# Aquarium_Nano.net
KiCad netlist of a schematic drawn in EAGLE
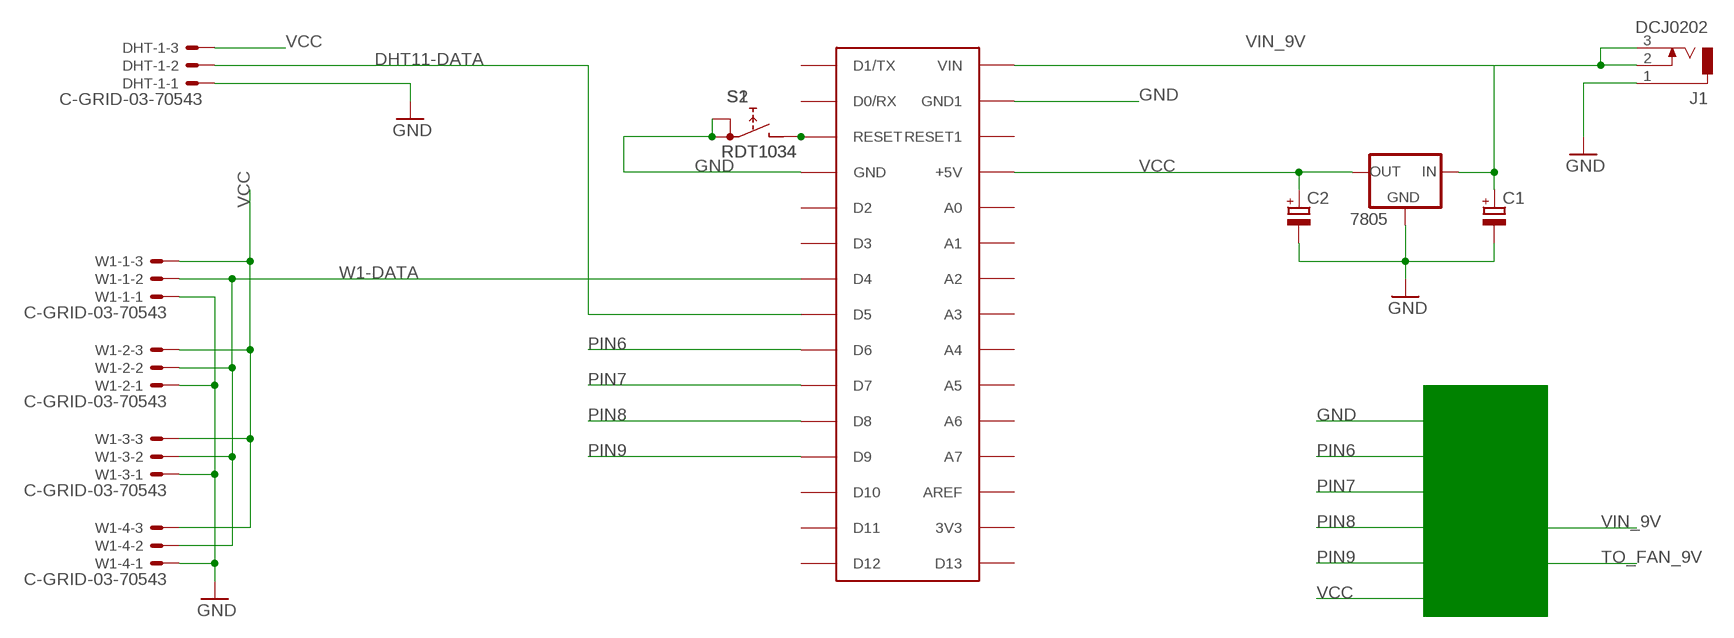
[diagram p0: schematic, sheet 1]

(export (version "E")
  (design (tool "Eeschema 10.0.6"))
  (components
    (comp (ref "7805")
      (value "V_REG_78XX-TO-220")
      (footprint "eagle-import:TO-220-ALT")
      (libsource (lib "eagle-import") (part "V_REG_78XX-TO-220"))
    )
    (comp (ref "C1")
      (value "CPOL-EUE2.5-6")
      (footprint "eagle-import:E2,5-6")
      (libsource (lib "eagle-import") (part "CPOL-EUE2.5-6"))
    )
    (comp (ref "C2")
      (value "CPOL-EUE2.5-6")
      (footprint "eagle-import:E2,5-6")
      (libsource (lib "eagle-import") (part "CPOL-EUE2.5-6"))
    )
    (comp (ref "DHT-1")
      (value "C-GRID-03-70543")
      (footprint "eagle-import:70543-03")
      (libsource (lib "eagle-import") (part "C-GRID-03-70543"))
    )
    (comp (ref "J1")
      (value "DCJ0202")
      (footprint "eagle-import:DCJ0202")
      (libsource (lib "eagle-import") (part "DCJ0202"))
    )
    (comp (ref "S1")
      (value "RDT1034")
      (footprint "eagle-import:RDT1034")
      (libsource (lib "eagle-import") (part "RDT1034"))
    )
    (comp (ref "S2")
      (value "RDT1034")
      (footprint "eagle-import:RDT1034")
      (libsource (lib "eagle-import") (part "RDT1034"))
    )
    (comp (ref "U$2")
      (value "ARDUINONANO")
      (footprint "eagle-import:PDIP-32")
      (libsource (lib "eagle-import") (part "ARDUINONANO"))
    )
    (comp (ref "W1-1")
      (value "C-GRID-03-70543")
      (footprint "eagle-import:70543-03")
      (libsource (lib "eagle-import") (part "C-GRID-03-70543"))
    )
    (comp (ref "W1-2")
      (value "C-GRID-03-70543")
      (footprint "eagle-import:70543-03")
      (libsource (lib "eagle-import") (part "C-GRID-03-70543"))
    )
    (comp (ref "W1-3")
      (value "C-GRID-03-70543")
      (footprint "eagle-import:70543-03")
      (libsource (lib "eagle-import") (part "C-GRID-03-70543"))
    )
    (comp (ref "W1-4")
      (value "C-GRID-03-70543")
      (footprint "eagle-import:70543-03")
      (libsource (lib "eagle-import") (part "C-GRID-03-70543"))
    )
  )
  (nets
    (net (code "1") (name "/DHT11-DATA") (class "Default")
      (node (ref "DHT-1") (pin "2") (pinfunction "S_2") (pintype "passive"))
      (node (ref "U$2") (pin "D5") (pinfunction "D5_D5") (pintype "bidirectional"))
    )
    (net (code "2") (name "/PIN6") (class "Default")
      (node (ref "U$2") (pin "D6") (pinfunction "D6_D6") (pintype "bidirectional"))
    )
    (net (code "3") (name "/PIN7") (class "Default")
      (node (ref "U$2") (pin "D7") (pinfunction "D7_D7") (pintype "bidirectional"))
    )
    (net (code "4") (name "/PIN8") (class "Default")
      (node (ref "U$2") (pin "D8") (pinfunction "D8_D8") (pintype "bidirectional"))
    )
    (net (code "5") (name "/PIN9") (class "Default")
      (node (ref "U$2") (pin "D9") (pinfunction "D9_D9") (pintype "bidirectional"))
    )
    (net (code "7") (name "/VCC") (class "Default")
      (node (ref "7805") (pin "OUT") (pinfunction "OUT_OUT") (pintype "output"))
      (node (ref "C2") (pin "+") (pinfunction "+_+") (pintype "passive"))
      (node (ref "DHT-1") (pin "3") (pinfunction "S_3") (pintype "passive"))
      (node (ref "U$2") (pin "+5V") (pinfunction "+5V_+5V") (pintype "bidirectional"))
      (node (ref "W1-1") (pin "3") (pinfunction "S_3") (pintype "passive"))
      (node (ref "W1-2") (pin "3") (pinfunction "S_3") (pintype "passive"))
      (node (ref "W1-3") (pin "3") (pinfunction "S_3") (pintype "passive"))
      (node (ref "W1-4") (pin "3") (pinfunction "S_3") (pintype "passive"))
    )
    (net (code "8") (name "/VIN_9V") (class "Default")
      (node (ref "7805") (pin "IN") (pinfunction "IN_IN") (pintype "input"))
      (node (ref "C1") (pin "+") (pinfunction "+_+") (pintype "passive"))
      (node (ref "J1") (pin "2") (pinfunction "2_2") (pintype "passive"))
      (node (ref "J1") (pin "3") (pinfunction "3_3") (pintype "passive"))
      (node (ref "U$2") (pin "VIN") (pinfunction "VIN_VIN") (pintype "bidirectional"))
    )
    (net (code "9") (name "/W1-DATA") (class "Default")
      (node (ref "U$2") (pin "D4") (pinfunction "D4_D4") (pintype "bidirectional"))
      (node (ref "W1-1") (pin "2") (pinfunction "S_2") (pintype "passive"))
      (node (ref "W1-2") (pin "2") (pinfunction "S_2") (pintype "passive"))
      (node (ref "W1-3") (pin "2") (pinfunction "S_2") (pintype "passive"))
      (node (ref "W1-4") (pin "2") (pinfunction "S_2") (pintype "passive"))
    )
    (net (code "10") (name "GND") (class "Default")
      (node (ref "7805") (pin "GND") (pinfunction "GND_GND") (pintype "input"))
      (node (ref "C1") (pin "-") (pinfunction "-_-") (pintype "passive"))
      (node (ref "C2") (pin "-") (pinfunction "-_-") (pintype "passive"))
      (node (ref "DHT-1") (pin "1") (pinfunction "S_1") (pintype "passive"))
      (node (ref "J1") (pin "1") (pinfunction "1_1") (pintype "passive"))
      (node (ref "S1") (pin "A") (pinfunction "A_A") (pintype "passive"))
      (node (ref "S1") (pin "A1") (pinfunction "A1_A1") (pintype "passive"))
      (node (ref "S2") (pin "A") (pinfunction "A_A") (pintype "passive"))
      (node (ref "S2") (pin "A1") (pinfunction "A1_A1") (pintype "passive"))
      (node (ref "U$2") (pin "GND") (pinfunction "GND_GND") (pintype "bidirectional"))
      (node (ref "U$2") (pin "GND1") (pinfunction "GND1_GND1") (pintype "bidirectional"))
      (node (ref "W1-1") (pin "1") (pinfunction "S_1") (pintype "passive"))
      (node (ref "W1-2") (pin "1") (pinfunction "S_1") (pintype "passive"))
      (node (ref "W1-3") (pin "1") (pinfunction "S_1") (pintype "passive"))
      (node (ref "W1-4") (pin "1") (pinfunction "S_1") (pintype "passive"))
    )
    (net (code "11") (name "Net-(S1-PadB)") (class "Default")
      (node (ref "S1") (pin "B") (pinfunction "B_B") (pintype "passive"))
      (node (ref "S2") (pin "B") (pinfunction "B_B") (pintype "passive"))
      (node (ref "U$2") (pin "RESET") (pinfunction "RESET_RESET") (pintype "bidirectional"))
    )
    (net (code "12") (name "unconnected-(U$2-Pad3V3)") (class "Default")
      (node (ref "U$2") (pin "3V3") (pinfunction "3V3_3V3") (pintype "bidirectional"))
    )
    (net (code "13") (name "unconnected-(U$2-PadA0)") (class "Default")
      (node (ref "U$2") (pin "A0") (pinfunction "A0_A0") (pintype "bidirectional"))
    )
    (net (code "14") (name "unconnected-(U$2-PadA1)") (class "Default")
      (node (ref "U$2") (pin "A1") (pinfunction "A1_A1") (pintype "bidirectional"))
    )
    (net (code "15") (name "unconnected-(U$2-PadA2)") (class "Default")
      (node (ref "U$2") (pin "A2") (pinfunction "A2_A2") (pintype "bidirectional"))
    )
    (net (code "16") (name "unconnected-(U$2-PadA3)") (class "Default")
      (node (ref "U$2") (pin "A3") (pinfunction "A3_A3") (pintype "bidirectional"))
    )
    (net (code "17") (name "unconnected-(U$2-PadA4)") (class "Default")
      (node (ref "U$2") (pin "A4") (pinfunction "A4_A4") (pintype "bidirectional"))
    )
    (net (code "18") (name "unconnected-(U$2-PadA5)") (class "Default")
      (node (ref "U$2") (pin "A5") (pinfunction "A5_A5") (pintype "bidirectional"))
    )
    (net (code "19") (name "unconnected-(U$2-PadA6)") (class "Default")
      (node (ref "U$2") (pin "A6") (pinfunction "A6_A6") (pintype "bidirectional"))
    )
    (net (code "20") (name "unconnected-(U$2-PadA7)") (class "Default")
      (node (ref "U$2") (pin "A7") (pinfunction "A7_A7") (pintype "bidirectional"))
    )
    (net (code "21") (name "unconnected-(U$2-PadAREF)") (class "Default")
      (node (ref "U$2") (pin "AREF") (pinfunction "AREF_AREF") (pintype "bidirectional"))
    )
    (net (code "22") (name "unconnected-(U$2-PadD0{slash}RX)") (class "Default")
      (node (ref "U$2") (pin "D0/RX") (pinfunction "D0/RX_D0/RX") (pintype "bidirectional"))
    )
    (net (code "23") (name "unconnected-(U$2-PadD1{slash}TX)") (class "Default")
      (node (ref "U$2") (pin "D1/TX") (pinfunction "D1/TX_D1/TX") (pintype "bidirectional"))
    )
    (net (code "24") (name "unconnected-(U$2-PadD2)") (class "Default")
      (node (ref "U$2") (pin "D2") (pinfunction "D2_D2") (pintype "bidirectional"))
    )
    (net (code "25") (name "unconnected-(U$2-PadD3)") (class "Default")
      (node (ref "U$2") (pin "D3") (pinfunction "D3_D3") (pintype "bidirectional"))
    )
    (net (code "26") (name "unconnected-(U$2-PadD10)") (class "Default")
      (node (ref "U$2") (pin "D10") (pinfunction "D10_D10") (pintype "bidirectional"))
    )
    (net (code "27") (name "unconnected-(U$2-PadD11)") (class "Default")
      (node (ref "U$2") (pin "D11") (pinfunction "D11_D11") (pintype "bidirectional"))
    )
    (net (code "28") (name "unconnected-(U$2-PadD12)") (class "Default")
      (node (ref "U$2") (pin "D12") (pinfunction "D12_D12") (pintype "bidirectional"))
    )
    (net (code "29") (name "unconnected-(U$2-PadD13)") (class "Default")
      (node (ref "U$2") (pin "D13") (pinfunction "D13_D13") (pintype "bidirectional"))
    )
    (net (code "30") (name "unconnected-(U$2-PadRESET1)") (class "Default")
      (node (ref "U$2") (pin "RESET1") (pinfunction "RESET1_RESET1") (pintype "bidirectional"))
    )
  )
)
